# nogyr.net
KiCad netlist of a schematic drawn in Altium Designer
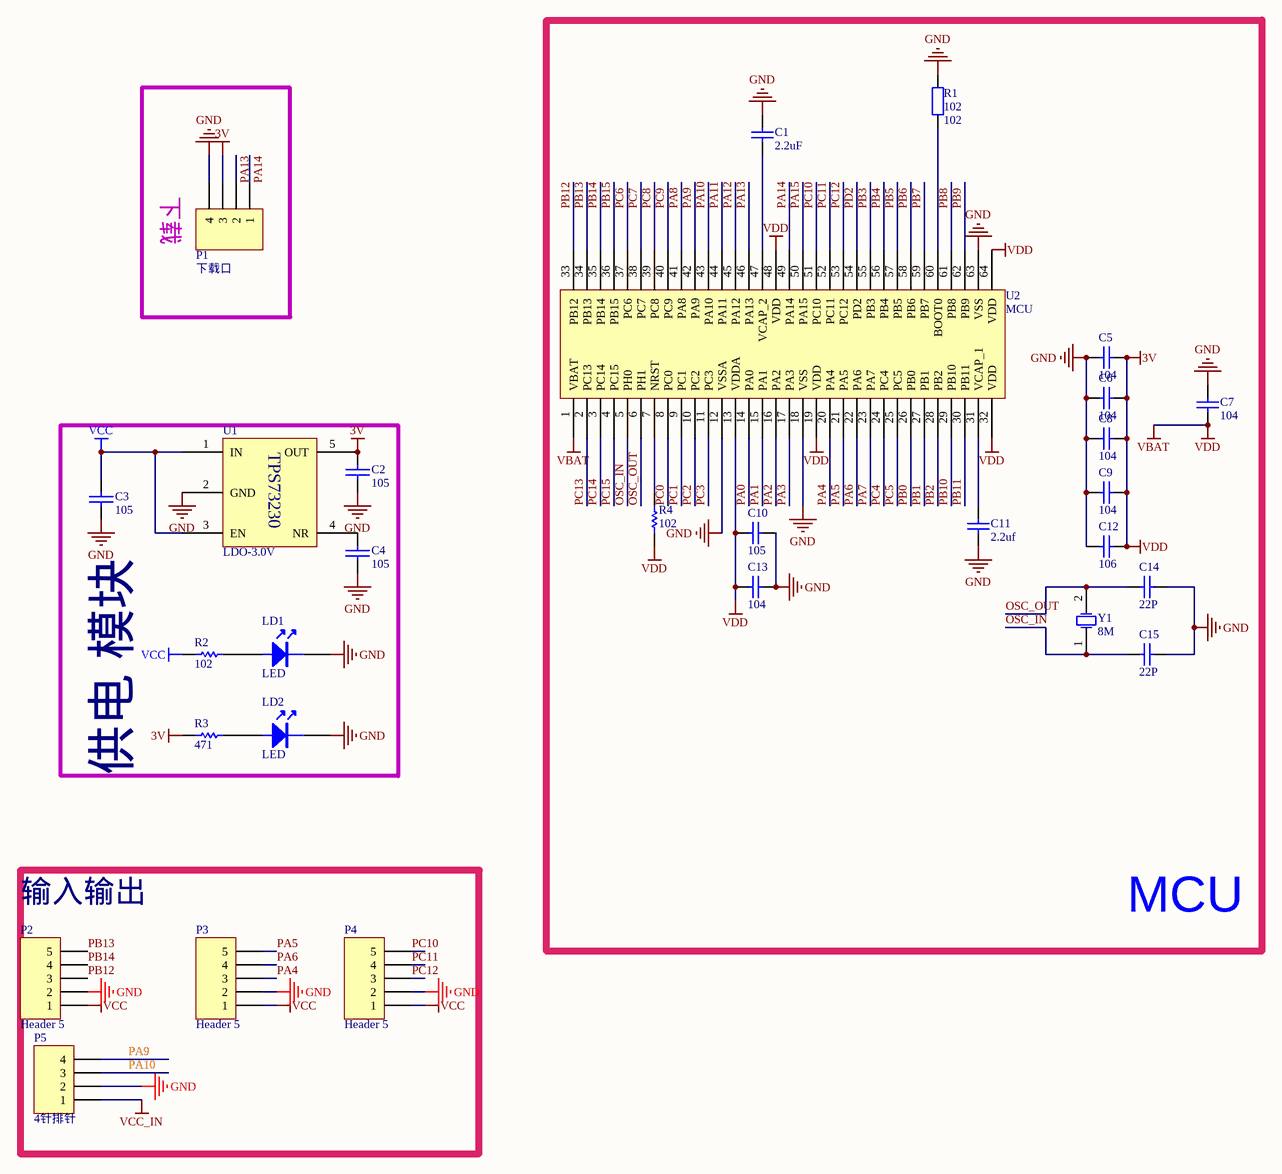
[diagram p0: nogyr.SchDoc]

(export (version "E")
  (design (tool "Eeschema 10.0.6"))
  (components
    (comp (ref "C1")
      (value "2.2uF")
      (footprint "C-0603C")
      (description "Capacitor")
      (fields (field (name "PUBLISHER") "Altium Limited"))
      (libsource (lib "Miscellaneous Devices") (part "Cap"))
    )
    (comp (ref "C2")
      (value "105")
      (footprint "C-0603C")
      (description "Capacitor")
      (libsource (lib "*") (part "CAP"))
    )
    (comp (ref "C3")
      (value "105")
      (footprint "C-0603C")
      (description "Capacitor")
      (libsource (lib "*") (part "CAP"))
    )
    (comp (ref "C4")
      (value "105")
      (footprint "C-0603C")
      (description "Capacitor")
      (libsource (lib "*") (part "CAP"))
    )
    (comp (ref "C5")
      (value "104")
      (footprint "C-0603C")
      (description "Capacitor")
      (fields (field (name "PUBLISHER") "Altium Limited"))
      (libsource (lib "Miscellaneous Devices") (part "Cap"))
    )
    (comp (ref "C6")
      (value "104")
      (footprint "C-0603C")
      (description "Capacitor")
      (fields (field (name "PUBLISHER") "Altium Limited"))
      (libsource (lib "Miscellaneous Devices") (part "Cap"))
    )
    (comp (ref "C7")
      (value "104")
      (footprint "C-0603C")
      (description "Capacitor")
      (fields (field (name "PUBLISHER") "Altium Limited"))
      (libsource (lib "Miscellaneous Devices") (part "Cap"))
    )
    (comp (ref "C8")
      (value "104")
      (footprint "C-0603C")
      (description "Capacitor")
      (fields (field (name "PUBLISHER") "Altium Limited"))
      (libsource (lib "Miscellaneous Devices") (part "Cap"))
    )
    (comp (ref "C9")
      (value "104")
      (footprint "C-0603C")
      (description "Capacitor")
      (fields (field (name "PUBLISHER") "Altium Limited"))
      (libsource (lib "Miscellaneous Devices") (part "Cap"))
    )
    (comp (ref "C10")
      (value "105")
      (footprint "C-0603C")
      (description "Capacitor")
      (fields (field (name "PUBLISHER") "Altium Limited"))
      (libsource (lib "Miscellaneous Devices") (part "Cap"))
    )
    (comp (ref "C11")
      (value "2.2uf")
      (footprint "C-0603C")
      (description "Capacitor")
      (fields (field (name "PUBLISHER") "Altium Limited"))
      (libsource (lib "Miscellaneous Devices") (part "Cap"))
    )
    (comp (ref "C12")
      (value "106")
      (footprint "C-0603C")
      (description "Capacitor")
      (fields (field (name "PUBLISHER") "Altium Limited"))
      (libsource (lib "Miscellaneous Devices") (part "Cap"))
    )
    (comp (ref "C13")
      (value "104")
      (footprint "C-0603C")
      (description "Capacitor")
      (fields (field (name "PUBLISHER") "Altium Limited"))
      (libsource (lib "Miscellaneous Devices") (part "Cap"))
    )
    (comp (ref "C14")
      (value "22P")
      (footprint "0603C")
      (description "Capacitor")
      (fields (field (name "PUBLISHER") "Altium Limited"))
      (libsource (lib "Miscellaneous Devices") (part "Cap"))
    )
    (comp (ref "C15")
      (value "22P")
      (footprint "0603C")
      (description "Capacitor")
      (fields (field (name "PUBLISHER") "Altium Limited"))
      (libsource (lib "Miscellaneous Devices") (part "Cap"))
    )
    (comp (ref "LD1") (value "LED") (footprint "0603C") (libsource (lib "PCB_Project1") (part "LED")))
    (comp (ref "LD2") (value "LED") (footprint "0603C") (libsource (lib "PCB_Project1") (part "LED")))
    (comp (ref "P1")
      (value "下载口")
      (footprint "HDR1X4")
      (description "Header, 4-Pin")
      (fields (field (name "PUBLISHER") "Altium Limited"))
      (libsource (lib "Miscellaneous Connectors") (part "Header 4"))
    )
    (comp (ref "P2")
      (value "Header 5")
      (footprint "FPC5-1.0")
      (description "Header, 5-Pin")
      (fields (field (name "PUBLISHER") "Altium Limited"))
      (libsource (lib "Miscellaneous Connectors") (part "Header 5"))
    )
    (comp (ref "P3")
      (value "Header 5")
      (footprint "FPC5-1.0")
      (description "Header, 5-Pin")
      (fields (field (name "PUBLISHER") "Altium Limited"))
      (libsource (lib "Miscellaneous Connectors") (part "Header 5"))
    )
    (comp (ref "P4")
      (value "Header 5")
      (footprint "FPC5-1.0")
      (description "Header, 5-Pin")
      (fields (field (name "PUBLISHER") "Altium Limited"))
      (libsource (lib "Miscellaneous Connectors") (part "Header 5"))
    )
    (comp (ref "P5")
      (value "4针排针")
      (footprint "HDR1X4")
      (description "Header, 4-Pin")
      (fields (field (name "PUBLISHER") "Altium Limited"))
      (libsource (lib "Integrated_Library1") (part "Header 4"))
    )
    (comp (ref "R1")
      (value "102")
      (footprint "C-0603C")
      (description "Resistor")
      (fields (field (name "ALTIUM_VALUE") "102") (field (name "PUBLISHER") "Altium Limited"))
      (libsource (lib "Miscellaneous Devices") (part "Res2"))
    )
    (comp (ref "R2")
      (value "102")
      (footprint "R-0603R")
      (description "Semiconductor Resistor")
      (fields (field (name "PUBLISHER") "Altium Limited"))
      (libsource (lib "大赛无线手柄") (part "Res Semi"))
    )
    (comp (ref "R3")
      (value "471")
      (footprint "R-0603R")
      (description "Semiconductor Resistor")
      (fields (field (name "PUBLISHER") "Altium Limited"))
      (libsource (lib "大赛无线手柄") (part "Res Semi"))
    )
    (comp (ref "R4")
      (value "102")
      (footprint "R-0603R")
      (description "Semiconductor Resistor")
      (fields (field (name "PUBLISHER") "Altium Limited"))
      (libsource (lib "大赛无线手柄") (part "Res Semi"))
    )
    (comp (ref "U1")
      (value "LDO-3.0V")
      (footprint "SOT-235")
      (description "TPS73230MDBVREP")
      (libsource (lib "GYR4") (part "TPS73230MDBVREP"))
    )
    (comp (ref "U2")
      (value "MCU")
      (footprint "LQFP64-STM32F405RG")
      (libsource (lib "陀螺仪 元件") (part "STM32F405RGT7"))
    )
    (comp (ref "Y1")
      (value "8M")
      (footprint "晶振-crystals")
      (description "Crystal Oscillator")
      (fields (field (name "PUBLISHER") "Altium Limited"))
      (libsource (lib "Miscellaneous Devices") (part "XTAL"))
    )
  )
  (nets
    (net (code "1") (name "/OSC_IN") (class "Default")
      (node (ref "C15") (pin "1") (pinfunction "1_1") (pintype "passive"))
      (node (ref "U2") (pin "5") (pinfunction "PH0_5") (pintype "passive"))
      (node (ref "Y1") (pin "1") (pinfunction "OSC1_1") (pintype "passive"))
    )
    (net (code "2") (name "/OSC_OUT") (class "Default")
      (node (ref "C14") (pin "1") (pinfunction "1_1") (pintype "passive"))
      (node (ref "U2") (pin "6") (pinfunction "PH1_6") (pintype "passive"))
      (node (ref "Y1") (pin "2") (pinfunction "OSC2_2") (pintype "passive"))
    )
    (net (code "3") (name "/PA0") (class "Default")
      (node (ref "U2") (pin "14") (pinfunction "PA0_14") (pintype "passive"))
    )
    (net (code "4") (name "/PA1") (class "Default")
      (node (ref "U2") (pin "15") (pinfunction "PA1_15") (pintype "passive"))
    )
    (net (code "5") (name "/PA2") (class "Default")
      (node (ref "U2") (pin "16") (pinfunction "PA2_16") (pintype "passive"))
    )
    (net (code "6") (name "/PA3") (class "Default")
      (node (ref "U2") (pin "17") (pinfunction "PA3_17") (pintype "passive"))
    )
    (net (code "7") (name "/PA4") (class "Default")
      (node (ref "P3") (pin "3") (pinfunction "3_3") (pintype "passive"))
      (node (ref "U2") (pin "20") (pinfunction "PA4_20") (pintype "passive"))
    )
    (net (code "8") (name "/PA5") (class "Default")
      (node (ref "P3") (pin "5") (pinfunction "5_5") (pintype "passive"))
      (node (ref "U2") (pin "21") (pinfunction "PA5_21") (pintype "passive"))
    )
    (net (code "9") (name "/PA6") (class "Default")
      (node (ref "P3") (pin "4") (pinfunction "4_4") (pintype "passive"))
      (node (ref "U2") (pin "22") (pinfunction "PA6_22") (pintype "passive"))
    )
    (net (code "10") (name "/PA7") (class "Default")
      (node (ref "U2") (pin "23") (pinfunction "PA7_23") (pintype "passive"))
    )
    (net (code "11") (name "/PA8") (class "Default")
      (node (ref "U2") (pin "41") (pinfunction "PA8_41") (pintype "passive"))
    )
    (net (code "12") (name "/PA9") (class "Default")
      (node (ref "P5") (pin "4") (pinfunction "4_4") (pintype "passive"))
      (node (ref "U2") (pin "42") (pinfunction "PA9_42") (pintype "passive"))
    )
    (net (code "13") (name "/PA10") (class "Default")
      (node (ref "P5") (pin "3") (pinfunction "3_3") (pintype "passive"))
      (node (ref "U2") (pin "43") (pinfunction "PA10_43") (pintype "passive"))
    )
    (net (code "14") (name "/PA11") (class "Default")
      (node (ref "U2") (pin "44") (pinfunction "PA11_44") (pintype "passive"))
    )
    (net (code "15") (name "/PA12") (class "Default")
      (node (ref "U2") (pin "45") (pinfunction "PA12_45") (pintype "passive"))
    )
    (net (code "16") (name "/PA13") (class "Default")
      (node (ref "P1") (pin "2") (pinfunction "2_2") (pintype "passive"))
      (node (ref "U2") (pin "46") (pinfunction "PA13_46") (pintype "passive"))
    )
    (net (code "17") (name "/PA14") (class "Default")
      (node (ref "P1") (pin "1") (pinfunction "1_1") (pintype "passive"))
      (node (ref "U2") (pin "49") (pinfunction "PA14_49") (pintype "passive"))
    )
    (net (code "18") (name "/PA15") (class "Default")
      (node (ref "U2") (pin "50") (pinfunction "PA15_50") (pintype "passive"))
    )
    (net (code "19") (name "/PB0") (class "Default")
      (node (ref "U2") (pin "26") (pinfunction "PB0_26") (pintype "passive"))
    )
    (net (code "20") (name "/PB1") (class "Default")
      (node (ref "U2") (pin "27") (pinfunction "PB1_27") (pintype "passive"))
    )
    (net (code "21") (name "/PB2") (class "Default")
      (node (ref "U2") (pin "28") (pinfunction "PB2_28") (pintype "passive"))
    )
    (net (code "22") (name "/PB3") (class "Default")
      (node (ref "U2") (pin "55") (pinfunction "PB3_55") (pintype "passive"))
    )
    (net (code "23") (name "/PB4") (class "Default")
      (node (ref "U2") (pin "56") (pinfunction "PB4_56") (pintype "passive"))
    )
    (net (code "24") (name "/PB5") (class "Default")
      (node (ref "U2") (pin "57") (pinfunction "PB5_57") (pintype "passive"))
    )
    (net (code "25") (name "/PB6") (class "Default")
      (node (ref "U2") (pin "58") (pinfunction "PB6_58") (pintype "passive"))
    )
    (net (code "26") (name "/PB7") (class "Default")
      (node (ref "U2") (pin "59") (pinfunction "PB7_59") (pintype "passive"))
    )
    (net (code "27") (name "/PB8") (class "Default")
      (node (ref "U2") (pin "61") (pinfunction "PB8_61") (pintype "passive"))
    )
    (net (code "28") (name "/PB9") (class "Default")
      (node (ref "U2") (pin "62") (pinfunction "PB9_62") (pintype "passive"))
    )
    (net (code "29") (name "/PB10") (class "Default")
      (node (ref "U2") (pin "29") (pinfunction "PB10_29") (pintype "passive"))
    )
    (net (code "30") (name "/PB11") (class "Default")
      (node (ref "U2") (pin "30") (pinfunction "PB11_30") (pintype "passive"))
    )
    (net (code "31") (name "/PB12") (class "Default")
      (node (ref "P2") (pin "3") (pinfunction "3_3") (pintype "passive"))
      (node (ref "U2") (pin "33") (pinfunction "PB12_33") (pintype "passive"))
    )
    (net (code "32") (name "/PB13") (class "Default")
      (node (ref "P2") (pin "5") (pinfunction "5_5") (pintype "passive"))
      (node (ref "U2") (pin "34") (pinfunction "PB13_34") (pintype "passive"))
    )
    (net (code "33") (name "/PB14") (class "Default")
      (node (ref "P2") (pin "4") (pinfunction "4_4") (pintype "passive"))
      (node (ref "U2") (pin "35") (pinfunction "PB14_35") (pintype "passive"))
    )
    (net (code "34") (name "/PB15") (class "Default")
      (node (ref "U2") (pin "36") (pinfunction "PB15_36") (pintype "passive"))
    )
    (net (code "35") (name "/PC0") (class "Default")
      (node (ref "U2") (pin "8") (pinfunction "PC0_8") (pintype "passive"))
    )
    (net (code "36") (name "/PC1") (class "Default")
      (node (ref "U2") (pin "9") (pinfunction "PC1_9") (pintype "passive"))
    )
    (net (code "37") (name "/PC2") (class "Default")
      (node (ref "U2") (pin "10") (pinfunction "PC2_10") (pintype "passive"))
    )
    (net (code "38") (name "/PC3") (class "Default")
      (node (ref "U2") (pin "11") (pinfunction "PC3_11") (pintype "passive"))
    )
    (net (code "39") (name "/PC4") (class "Default")
      (node (ref "U2") (pin "24") (pinfunction "PC4_24") (pintype "passive"))
    )
    (net (code "40") (name "/PC5") (class "Default")
      (node (ref "U2") (pin "25") (pinfunction "PC5_25") (pintype "passive"))
    )
    (net (code "41") (name "/PC6") (class "Default")
      (node (ref "U2") (pin "37") (pinfunction "PC6_37") (pintype "passive"))
    )
    (net (code "42") (name "/PC7") (class "Default")
      (node (ref "U2") (pin "38") (pinfunction "PC7_38") (pintype "passive"))
    )
    (net (code "43") (name "/PC8") (class "Default")
      (node (ref "U2") (pin "39") (pinfunction "PC8_39") (pintype "passive"))
    )
    (net (code "44") (name "/PC9") (class "Default")
      (node (ref "U2") (pin "40") (pinfunction "PC9_40") (pintype "passive"))
    )
    (net (code "45") (name "/PC10") (class "Default")
      (node (ref "P4") (pin "5") (pinfunction "5_5") (pintype "passive"))
      (node (ref "U2") (pin "51") (pinfunction "PC10_51") (pintype "passive"))
    )
    (net (code "46") (name "/PC11") (class "Default")
      (node (ref "P4") (pin "4") (pinfunction "4_4") (pintype "passive"))
      (node (ref "U2") (pin "52") (pinfunction "PC11_52") (pintype "passive"))
    )
    (net (code "47") (name "/PC12") (class "Default")
      (node (ref "P4") (pin "3") (pinfunction "3_3") (pintype "passive"))
      (node (ref "U2") (pin "53") (pinfunction "PC12_53") (pintype "passive"))
    )
    (net (code "48") (name "/PC13") (class "Default")
      (node (ref "U2") (pin "2") (pinfunction "PC13_2") (pintype "passive"))
    )
    (net (code "49") (name "/PC14") (class "Default")
      (node (ref "U2") (pin "3") (pinfunction "PC14_3") (pintype "passive"))
    )
    (net (code "50") (name "/PC15") (class "Default")
      (node (ref "U2") (pin "4") (pinfunction "PC15_4") (pintype "passive"))
    )
    (net (code "51") (name "/PD2") (class "Default")
      (node (ref "U2") (pin "54") (pinfunction "PD2_54") (pintype "passive"))
    )
    (net (code "52") (name "3V") (class "Default")
      (node (ref "C10") (pin "1") (pinfunction "1_1") (pintype "passive"))
      (node (ref "C12") (pin "1") (pinfunction "1_1") (pintype "passive"))
      (node (ref "C13") (pin "1") (pinfunction "1_1") (pintype "passive"))
      (node (ref "C2") (pin "1") (pinfunction "1_1") (pintype "passive"))
      (node (ref "C5") (pin "1") (pinfunction "1_1") (pintype "passive"))
      (node (ref "C6") (pin "1") (pinfunction "1_1") (pintype "passive"))
      (node (ref "C7") (pin "1") (pinfunction "1_1") (pintype "passive"))
      (node (ref "C8") (pin "1") (pinfunction "1_1") (pintype "passive"))
      (node (ref "C9") (pin "1") (pinfunction "1_1") (pintype "passive"))
      (node (ref "P1") (pin "3") (pinfunction "3_3") (pintype "passive"))
      (node (ref "R3") (pin "1") (pinfunction "1_1") (pintype "passive"))
      (node (ref "R4") (pin "2") (pinfunction "2_2") (pintype "passive"))
      (node (ref "U1") (pin "5") (pinfunction "OUT_5") (pintype "passive"))
      (node (ref "U2") (pin "1") (pinfunction "VBAT_1") (pintype "passive"))
      (node (ref "U2") (pin "13") (pinfunction "VDDA_13") (pintype "passive"))
      (node (ref "U2") (pin "19") (pinfunction "VDD_19") (pintype "passive"))
      (node (ref "U2") (pin "32") (pinfunction "VDD_32") (pintype "passive"))
      (node (ref "U2") (pin "48") (pinfunction "VDD_48") (pintype "passive"))
      (node (ref "U2") (pin "64") (pinfunction "VDD_64") (pintype "passive"))
    )
    (net (code "53") (name "GND") (class "Default")
      (node (ref "C1") (pin "2") (pinfunction "2_2") (pintype "passive"))
      (node (ref "C10") (pin "2") (pinfunction "2_2") (pintype "passive"))
      (node (ref "C11") (pin "1") (pinfunction "1_1") (pintype "passive"))
      (node (ref "C12") (pin "2") (pinfunction "2_2") (pintype "passive"))
      (node (ref "C13") (pin "2") (pinfunction "2_2") (pintype "passive"))
      (node (ref "C14") (pin "2") (pinfunction "2_2") (pintype "passive"))
      (node (ref "C15") (pin "2") (pinfunction "2_2") (pintype "passive"))
      (node (ref "C2") (pin "2") (pinfunction "2_2") (pintype "passive"))
      (node (ref "C3") (pin "2") (pinfunction "2_2") (pintype "passive"))
      (node (ref "C4") (pin "2") (pinfunction "2_2") (pintype "passive"))
      (node (ref "C5") (pin "2") (pinfunction "2_2") (pintype "passive"))
      (node (ref "C6") (pin "2") (pinfunction "2_2") (pintype "passive"))
      (node (ref "C7") (pin "2") (pinfunction "2_2") (pintype "passive"))
      (node (ref "C8") (pin "2") (pinfunction "2_2") (pintype "passive"))
      (node (ref "C9") (pin "2") (pinfunction "2_2") (pintype "passive"))
      (node (ref "LD1") (pin "K") (pinfunction "2_K") (pintype "passive"))
      (node (ref "LD2") (pin "K") (pinfunction "2_K") (pintype "passive"))
      (node (ref "P1") (pin "4") (pinfunction "4_4") (pintype "passive"))
      (node (ref "P2") (pin "2") (pinfunction "2_2") (pintype "passive"))
      (node (ref "P3") (pin "2") (pinfunction "2_2") (pintype "passive"))
      (node (ref "P4") (pin "2") (pinfunction "2_2") (pintype "passive"))
      (node (ref "P5") (pin "2") (pinfunction "2_2") (pintype "passive"))
      (node (ref "R1") (pin "2") (pinfunction "2_2") (pintype "passive"))
      (node (ref "U1") (pin "2") (pinfunction "GND_2") (pintype "passive"))
      (node (ref "U2") (pin "12") (pinfunction "VSSA_12") (pintype "passive"))
      (node (ref "U2") (pin "18") (pinfunction "VSS_18") (pintype "passive"))
      (node (ref "U2") (pin "63") (pinfunction "VSS_63") (pintype "passive"))
    )
    (net (code "54") (name "Net-(LD1-1)") (class "Default")
      (node (ref "LD1") (pin "A") (pinfunction "1_A") (pintype "passive"))
      (node (ref "R2") (pin "2") (pinfunction "2_2") (pintype "passive"))
    )
    (net (code "55") (name "Net-(LD2-1)") (class "Default")
      (node (ref "LD2") (pin "A") (pinfunction "1_A") (pintype "passive"))
      (node (ref "R3") (pin "2") (pinfunction "2_2") (pintype "passive"))
    )
    (net (code "56") (name "Net-(U1-NR)") (class "Default")
      (node (ref "C4") (pin "1") (pinfunction "1_1") (pintype "passive"))
      (node (ref "U1") (pin "4") (pinfunction "NR_4") (pintype "passive"))
    )
    (net (code "57") (name "Net-(U2-BOOT0)") (class "Default")
      (node (ref "R1") (pin "1") (pinfunction "1_1") (pintype "passive"))
      (node (ref "U2") (pin "60") (pinfunction "BOOT0_60") (pintype "passive"))
    )
    (net (code "58") (name "Net-(U2-NRST)") (class "Default")
      (node (ref "R4") (pin "1") (pinfunction "1_1") (pintype "passive"))
      (node (ref "U2") (pin "7") (pinfunction "NRST_7") (pintype "passive"))
    )
    (net (code "59") (name "Net-(U2-VCAP_1)") (class "Default")
      (node (ref "C11") (pin "2") (pinfunction "2_2") (pintype "passive"))
      (node (ref "U2") (pin "31") (pinfunction "VCAP_1_31") (pintype "passive"))
    )
    (net (code "60") (name "Net-(U2-VCAP_2)") (class "Default")
      (node (ref "C1") (pin "1") (pinfunction "1_1") (pintype "passive"))
      (node (ref "U2") (pin "47") (pinfunction "VCAP_2_47") (pintype "passive"))
    )
    (net (code "61") (name "VCC") (class "Default")
      (node (ref "C3") (pin "1") (pinfunction "1_1") (pintype "passive"))
      (node (ref "P2") (pin "1") (pinfunction "1_1") (pintype "passive"))
      (node (ref "P3") (pin "1") (pinfunction "1_1") (pintype "passive"))
      (node (ref "P4") (pin "1") (pinfunction "1_1") (pintype "passive"))
      (node (ref "R2") (pin "1") (pinfunction "1_1") (pintype "passive"))
      (node (ref "U1") (pin "1") (pinfunction "IN_1") (pintype "passive"))
      (node (ref "U1") (pin "3") (pinfunction "EN_3") (pintype "passive"))
    )
    (net (code "62") (name "VCC_IN") (class "Default")
      (node (ref "P5") (pin "1") (pinfunction "1_1") (pintype "passive"))
    )
  )
)
